# POWER.net
KiCad netlist of a schematic drawn in Altium Designer
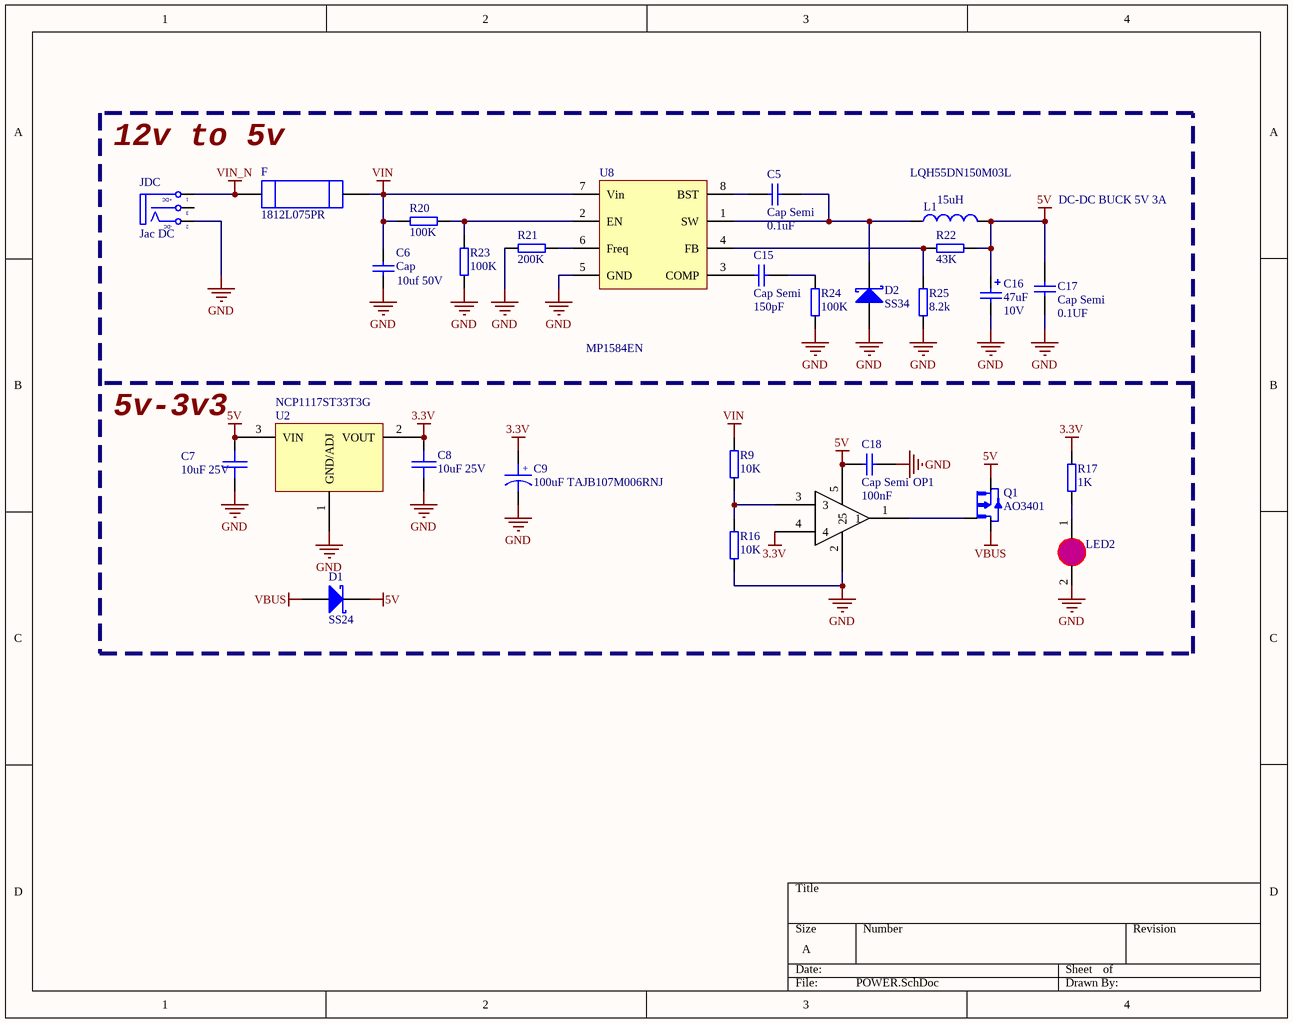
[diagram p0: POWER.SchDoc]

(export (version "E")
  (design (tool "Eeschema 10.0.6"))
  (components
    (comp (ref "C5")
      (value "Cap Semi")
      (footprint "SMT0603")
      (description "CAP SM 0603 X5R 10uF 10%")
      (fields (field (name "TOLERANCE") "±10%") (field (name "ALTIUM_VALUE") "0.1uF"))
      (libsource (lib "electronpowered") (part "CAP-SM-0603-X5R-10uF"))
    )
    (comp (ref "C6")
      (value "Cap")
      (footprint "1206")
      (description "Capacitor")
      (fields (field (name "ALTIUM_VALUE") "10uf 50V") (field (name "PUBLISHER") "Altium Limited"))
      (libsource (lib "Miscellaneous Devices") (part "Cap"))
    )
    (comp (ref "C7")
      (value "10uF 25V")
      (footprint "SMT_C_0805")
      (description "Surface mount capacitor 0805")
      (libsource (lib "NODEMCU_DEVKIT_V1.0") (part "SMT_C_0805"))
    )
    (comp (ref "C8")
      (value "10uF 25V")
      (footprint "SMT_C_0805")
      (description "Surface mount capacitor 0805")
      (libsource (lib "NODEMCU_DEVKIT_V1.0") (part "SMT_C_0805"))
    )
    (comp (ref "C9")
      (value "100uF TAJB107M006RNJ")
      (footprint "SMT_C_Tantalum_B")
      (description "Capacitor, SM Tantalum; Body 3.5 x 2.8 mm (LxW typ)")
      (libsource (lib "NODEMCU_DEVKIT_V1.0") (part "SMT_C_Tantalum_B"))
    )
    (comp (ref "C15")
      (value "Cap Semi")
      (footprint "SMT0603")
      (description "CAP SM 0603 X5R 10uF 10%")
      (fields (field (name "TOLERANCE") "±10%") (field (name "ALTIUM_VALUE") "150pF"))
      (libsource (lib "electronpowered") (part "CAP-SM-0603-X5R-10uF"))
    )
    (comp (ref "C16")
      (value "47uF")
      (footprint "Tantal_B")
      (description "Polarized Capacitor (Axial)")
      (fields (field (name "VOLTAGE") "10V") (field (name "PUBLISHER") "Altium Limited"))
      (libsource (lib "mp1584") (part "Cap Pol"))
    )
    (comp (ref "C17")
      (value "Cap Semi")
      (footprint "SMT0603")
      (description "CAP SM 0603 X5R 10uF 10%")
      (fields (field (name "TOLERANCE") "±10%") (field (name "ALTIUM_VALUE") "0.1UF"))
      (libsource (lib "electronpowered") (part "CAP-SM-0603-X5R-10uF"))
    )
    (comp (ref "C18")
      (value "Cap Semi")
      (footprint "SMT0603")
      (description "CAP SM 0603 X7R 100nF 10%")
      (fields (field (name "TOLERANCE") "±10%") (field (name "ALTIUM_VALUE") "100nF"))
      (libsource (lib "electronpowered") (part "CAP-SM-0603-X7R-100nF"))
    )
    (comp (ref "D1")
      (value "SS24")
      (footprint "SMB")
      (description "Schottky Diode")
      (fields (field (name "PUBLISHER") "Altium Limited"))
      (libsource (lib "mp1584") (part "D Schottky"))
    )
    (comp (ref "D2")
      (value "SS34")
      (footprint "SMB")
      (description "Schottky Diode")
      (fields (field (name "PUBLISHER") "Altium Limited"))
      (libsource (lib "mp1584") (part "D Schottky"))
    )
    (comp (ref "F")
      (value "1812L075PR")
      (footprint "1812")
      (description "Polymeric PTC Resettable Fuse 13.2V 750mA Ih Surface Mount 1812 _4532 Metric_, Concave")
      (fields (field (name "MF") "Littelfuse Inc."))
      (libsource (lib "1812L075PR") (part "1812L075PR"))
    )
    (comp (ref "JDC")
      (value "Jac DC")
      (footprint "DC-IN")
      (description "Jac DC input")
      (libsource (lib "My Library") (part "DCIN"))
    )
    (comp (ref "L1")
      (value "15uH")
      (footprint "Inductor SMD 6.8*6.8*4.5")
      (fields (field (name "MARKA") "LQH55DN150M03L"))
      (libsource (lib "mp1584") (part "Inductor"))
    )
    (comp (ref "LED2")
      (value "LED3")
      (footprint "LED0805")
      (description "LED SMD 0805")
      (libsource (lib "My Library") (part "LED0805"))
    )
    (comp (ref "OP1")
      (value "Component_1")
      (footprint "SOT23-5")
      (libsource (lib "mcp601ot") (part "Component_1"))
    )
    (comp (ref "Q1")
      (value "AO3401")
      (footprint "SOT23")
      (description "P-Channel 30V 4A _Ta_ 1.4W _Ta_ Surface Mount SOT-23-3")
      (fields (field (name "MF") "Alpha & Omega Semiconductor"))
      (libsource (lib "AO3401") (part "AO3401"))
    )
    (comp (ref "R9")
      (value "10K")
      (footprint "SMT0603")
      (description "RES SM 0603 10K")
      (fields (field (name "Comment") "Resistor"))
      (libsource (lib "electronpowered") (part "RES-SM-0603-10K"))
    )
    (comp (ref "R16")
      (value "10K")
      (footprint "SMT0603")
      (description "RES SM 0603 10K")
      (fields (field (name "Comment") "Resistor"))
      (libsource (lib "electronpowered") (part "RES-SM-0603-10K"))
    )
    (comp (ref "R17")
      (value "1K")
      (footprint "SMT0603")
      (description "RES SM 0603 100K")
      (fields (field (name "Comment") "Resistor"))
      (libsource (lib "electronpowered") (part "RES-SM-0603-100K"))
    )
    (comp (ref "R20")
      (value "100K")
      (footprint "SMT0603")
      (description "RES SM 0603 100K")
      (fields (field (name "Comment") "Resistor"))
      (libsource (lib "electronpowered") (part "RES-SM-0603-100K"))
    )
    (comp (ref "R21")
      (value "200K")
      (footprint "SMT0603")
      (description "RES SM 0603 100K")
      (fields (field (name "Comment") "Resistor"))
      (libsource (lib "electronpowered") (part "RES-SM-0603-100K"))
    )
    (comp (ref "R22")
      (value "43K")
      (footprint "SMT0603")
      (description "RES SM 0603 100K")
      (fields (field (name "Comment") "Resistor"))
      (libsource (lib "electronpowered") (part "RES-SM-0603-100K"))
    )
    (comp (ref "R23")
      (value "100K")
      (footprint "SMT0603")
      (description "RES SM 0603 100K")
      (fields (field (name "Comment") "Resistor"))
      (libsource (lib "electronpowered") (part "RES-SM-0603-100K"))
    )
    (comp (ref "R24")
      (value "100K")
      (footprint "SMT0603")
      (description "RES SM 0603 100K")
      (fields (field (name "Comment") "Resistor"))
      (libsource (lib "electronpowered") (part "RES-SM-0603-100K"))
    )
    (comp (ref "R25")
      (value "8.2k")
      (footprint "SMT0603")
      (description "RES SM 0603 100K")
      (fields (field (name "Comment") "Resistor"))
      (libsource (lib "electronpowered") (part "RES-SM-0603-100K"))
    )
    (comp (ref "U2")
      (value "NCP1117ST33T3G")
      (footprint "SOT-223")
      (description "NCP1117, NCV1117. 1.0 A Low-Dropout Positive  Fixed and Adjustable  Voltage Regulators")
      (libsource (lib "NODEMCU_DEVKIT_V1.0") (part "NCP1117"))
    )
    (comp (ref "U8") (value "MP1584EN") (footprint "SO-8") (libsource (lib "mp1584") (part "MP1584")))
  )
  (nets
    (net (code "1") (name "3.3V") (class "Default")
      (node (ref "C8") (pin "1") (pinfunction "1_1") (pintype "passive"))
      (node (ref "C9") (pin "1") (pinfunction "1_1") (pintype "passive"))
      (node (ref "OP1") (pin "4") (pinfunction "4_4") (pintype "passive"))
      (node (ref "R17") (pin "1") (pinfunction "1_1") (pintype "passive"))
      (node (ref "U2") (pin "2") (pinfunction "VOUT_2") (pintype "passive"))
    )
    (net (code "2") (name "5V") (class "Default")
      (node (ref "C16") (pin "1") (pinfunction "1_1") (pintype "passive"))
      (node (ref "C17") (pin "1") (pinfunction "1_1") (pintype "passive"))
      (node (ref "C18") (pin "1") (pinfunction "1_1") (pintype "passive"))
      (node (ref "C7") (pin "1") (pinfunction "1_1") (pintype "passive"))
      (node (ref "D1") (pin "2") (pinfunction "K_2") (pintype "passive"))
      (node (ref "L1") (pin "2") (pinfunction "2_2") (pintype "passive"))
      (node (ref "OP1") (pin "5") (pinfunction "5_5") (pintype "passive"))
      (node (ref "Q1") (pin "2") (pinfunction "S_2") (pintype "passive"))
      (node (ref "R22") (pin "1") (pinfunction "1_1") (pintype "passive"))
      (node (ref "U2") (pin "3") (pinfunction "VIN_3") (pintype "passive"))
    )
    (net (code "3") (name "GND") (class "Default")
      (node (ref "C16") (pin "2") (pinfunction "2_2") (pintype "passive"))
      (node (ref "C17") (pin "2") (pinfunction "2_2") (pintype "passive"))
      (node (ref "C18") (pin "2") (pinfunction "2_2") (pintype "passive"))
      (node (ref "C6") (pin "2") (pinfunction "2_2") (pintype "passive"))
      (node (ref "C7") (pin "2") (pinfunction "2_2") (pintype "passive"))
      (node (ref "C8") (pin "2") (pinfunction "2_2") (pintype "passive"))
      (node (ref "C9") (pin "2") (pinfunction "2_2") (pintype "passive"))
      (node (ref "D2") (pin "1") (pinfunction "A_1") (pintype "passive"))
      (node (ref "JDC") (pin "2") (pinfunction "TN_2") (pintype "passive"))
      (node (ref "LED2") (pin "2") (pinfunction "K_2") (pintype "passive"))
      (node (ref "OP1") (pin "2") (pinfunction "2_2") (pintype "passive"))
      (node (ref "R16") (pin "1") (pinfunction "1_1") (pintype "passive"))
      (node (ref "R21") (pin "1") (pinfunction "1_1") (pintype "passive"))
      (node (ref "R23") (pin "2") (pinfunction "2_2") (pintype "passive"))
      (node (ref "R24") (pin "1") (pinfunction "1_1") (pintype "passive"))
      (node (ref "R25") (pin "2") (pinfunction "2_2") (pintype "passive"))
      (node (ref "U2") (pin "1") (pinfunction "GND/ADJ_1") (pintype "passive"))
      (node (ref "U8") (pin "5") (pinfunction "GND_5") (pintype "passive"))
    )
    (net (code "4") (name "Net-(C15-Pad1)") (class "Default")
      (node (ref "C15") (pin "1") (pinfunction "1_1") (pintype "passive"))
      (node (ref "R24") (pin "2") (pinfunction "2_2") (pintype "passive"))
    )
    (net (code "5") (name "Net-(D2-K)") (class "Default")
      (node (ref "C5") (pin "1") (pinfunction "1_1") (pintype "passive"))
      (node (ref "D2") (pin "2") (pinfunction "K_2") (pintype "passive"))
      (node (ref "L1") (pin "1") (pinfunction "1_1") (pintype "passive"))
      (node (ref "U8") (pin "1") (pinfunction "SW_1") (pintype "passive"))
    )
    (net (code "6") (name "Net-(LED2-A)") (class "Default")
      (node (ref "LED2") (pin "1") (pinfunction "A_1") (pintype "passive"))
      (node (ref "R17") (pin "2") (pinfunction "2_2") (pintype "passive"))
    )
    (net (code "7") (name "Net-(OP1-Pad3)") (class "Default")
      (node (ref "OP1") (pin "3") (pinfunction "3_3") (pintype "passive"))
      (node (ref "R16") (pin "2") (pinfunction "2_2") (pintype "passive"))
      (node (ref "R9") (pin "1") (pinfunction "1_1") (pintype "passive"))
    )
    (net (code "8") (name "Net-(Q1-G)") (class "Default")
      (node (ref "OP1") (pin "1") (pinfunction "1_1") (pintype "passive"))
      (node (ref "Q1") (pin "1") (pinfunction "G_1") (pintype "passive"))
    )
    (net (code "9") (name "Net-(U8-BST)") (class "Default")
      (node (ref "C5") (pin "2") (pinfunction "2_2") (pintype "passive"))
      (node (ref "U8") (pin "8") (pinfunction "BST_8") (pintype "passive"))
    )
    (net (code "10") (name "Net-(U8-COMP)") (class "Default")
      (node (ref "C15") (pin "2") (pinfunction "2_2") (pintype "passive"))
      (node (ref "U8") (pin "3") (pinfunction "COMP_3") (pintype "passive"))
    )
    (net (code "11") (name "Net-(U8-EN)") (class "Default")
      (node (ref "R20") (pin "2") (pinfunction "2_2") (pintype "passive"))
      (node (ref "R23") (pin "1") (pinfunction "1_1") (pintype "passive"))
      (node (ref "U8") (pin "2") (pinfunction "EN_2") (pintype "passive"))
    )
    (net (code "12") (name "Net-(U8-FB)") (class "Default")
      (node (ref "R22") (pin "2") (pinfunction "2_2") (pintype "passive"))
      (node (ref "R25") (pin "1") (pinfunction "1_1") (pintype "passive"))
      (node (ref "U8") (pin "4") (pinfunction "FB_4") (pintype "passive"))
    )
    (net (code "13") (name "Net-(U8-Freq)") (class "Default")
      (node (ref "R21") (pin "2") (pinfunction "2_2") (pintype "passive"))
      (node (ref "U8") (pin "6") (pinfunction "Freq_6") (pintype "passive"))
    )
    (net (code "14") (name "VBUS") (class "Default")
      (node (ref "D1") (pin "1") (pinfunction "A_1") (pintype "passive"))
      (node (ref "Q1") (pin "3") (pinfunction "D_3") (pintype "passive"))
    )
    (net (code "15") (name "VIN") (class "Default")
      (node (ref "C6") (pin "1") (pinfunction "1_1") (pintype "passive"))
      (node (ref "F") (pin "2") (pinfunction "2_2") (pintype "passive"))
      (node (ref "R20") (pin "1") (pinfunction "1_1") (pintype "passive"))
      (node (ref "R9") (pin "2") (pinfunction "2_2") (pintype "passive"))
      (node (ref "U8") (pin "7") (pinfunction "Vin_7") (pintype "passive"))
    )
    (net (code "16") (name "VIN_N") (class "Default")
      (node (ref "F") (pin "1") (pinfunction "1_1") (pintype "passive"))
      (node (ref "JDC") (pin "1") (pinfunction "T_1") (pintype "passive"))
    )
    (net (code "17") (name "unconnected-(JDC-S-Pad3)") (class "Default")
      (node (ref "JDC") (pin "3") (pinfunction "S_3") (pintype "power_in"))
    )
  )
)
